# stm32f405rgt6_DB_Sheet.net
KiCad netlist of a schematic drawn in Altium Designer
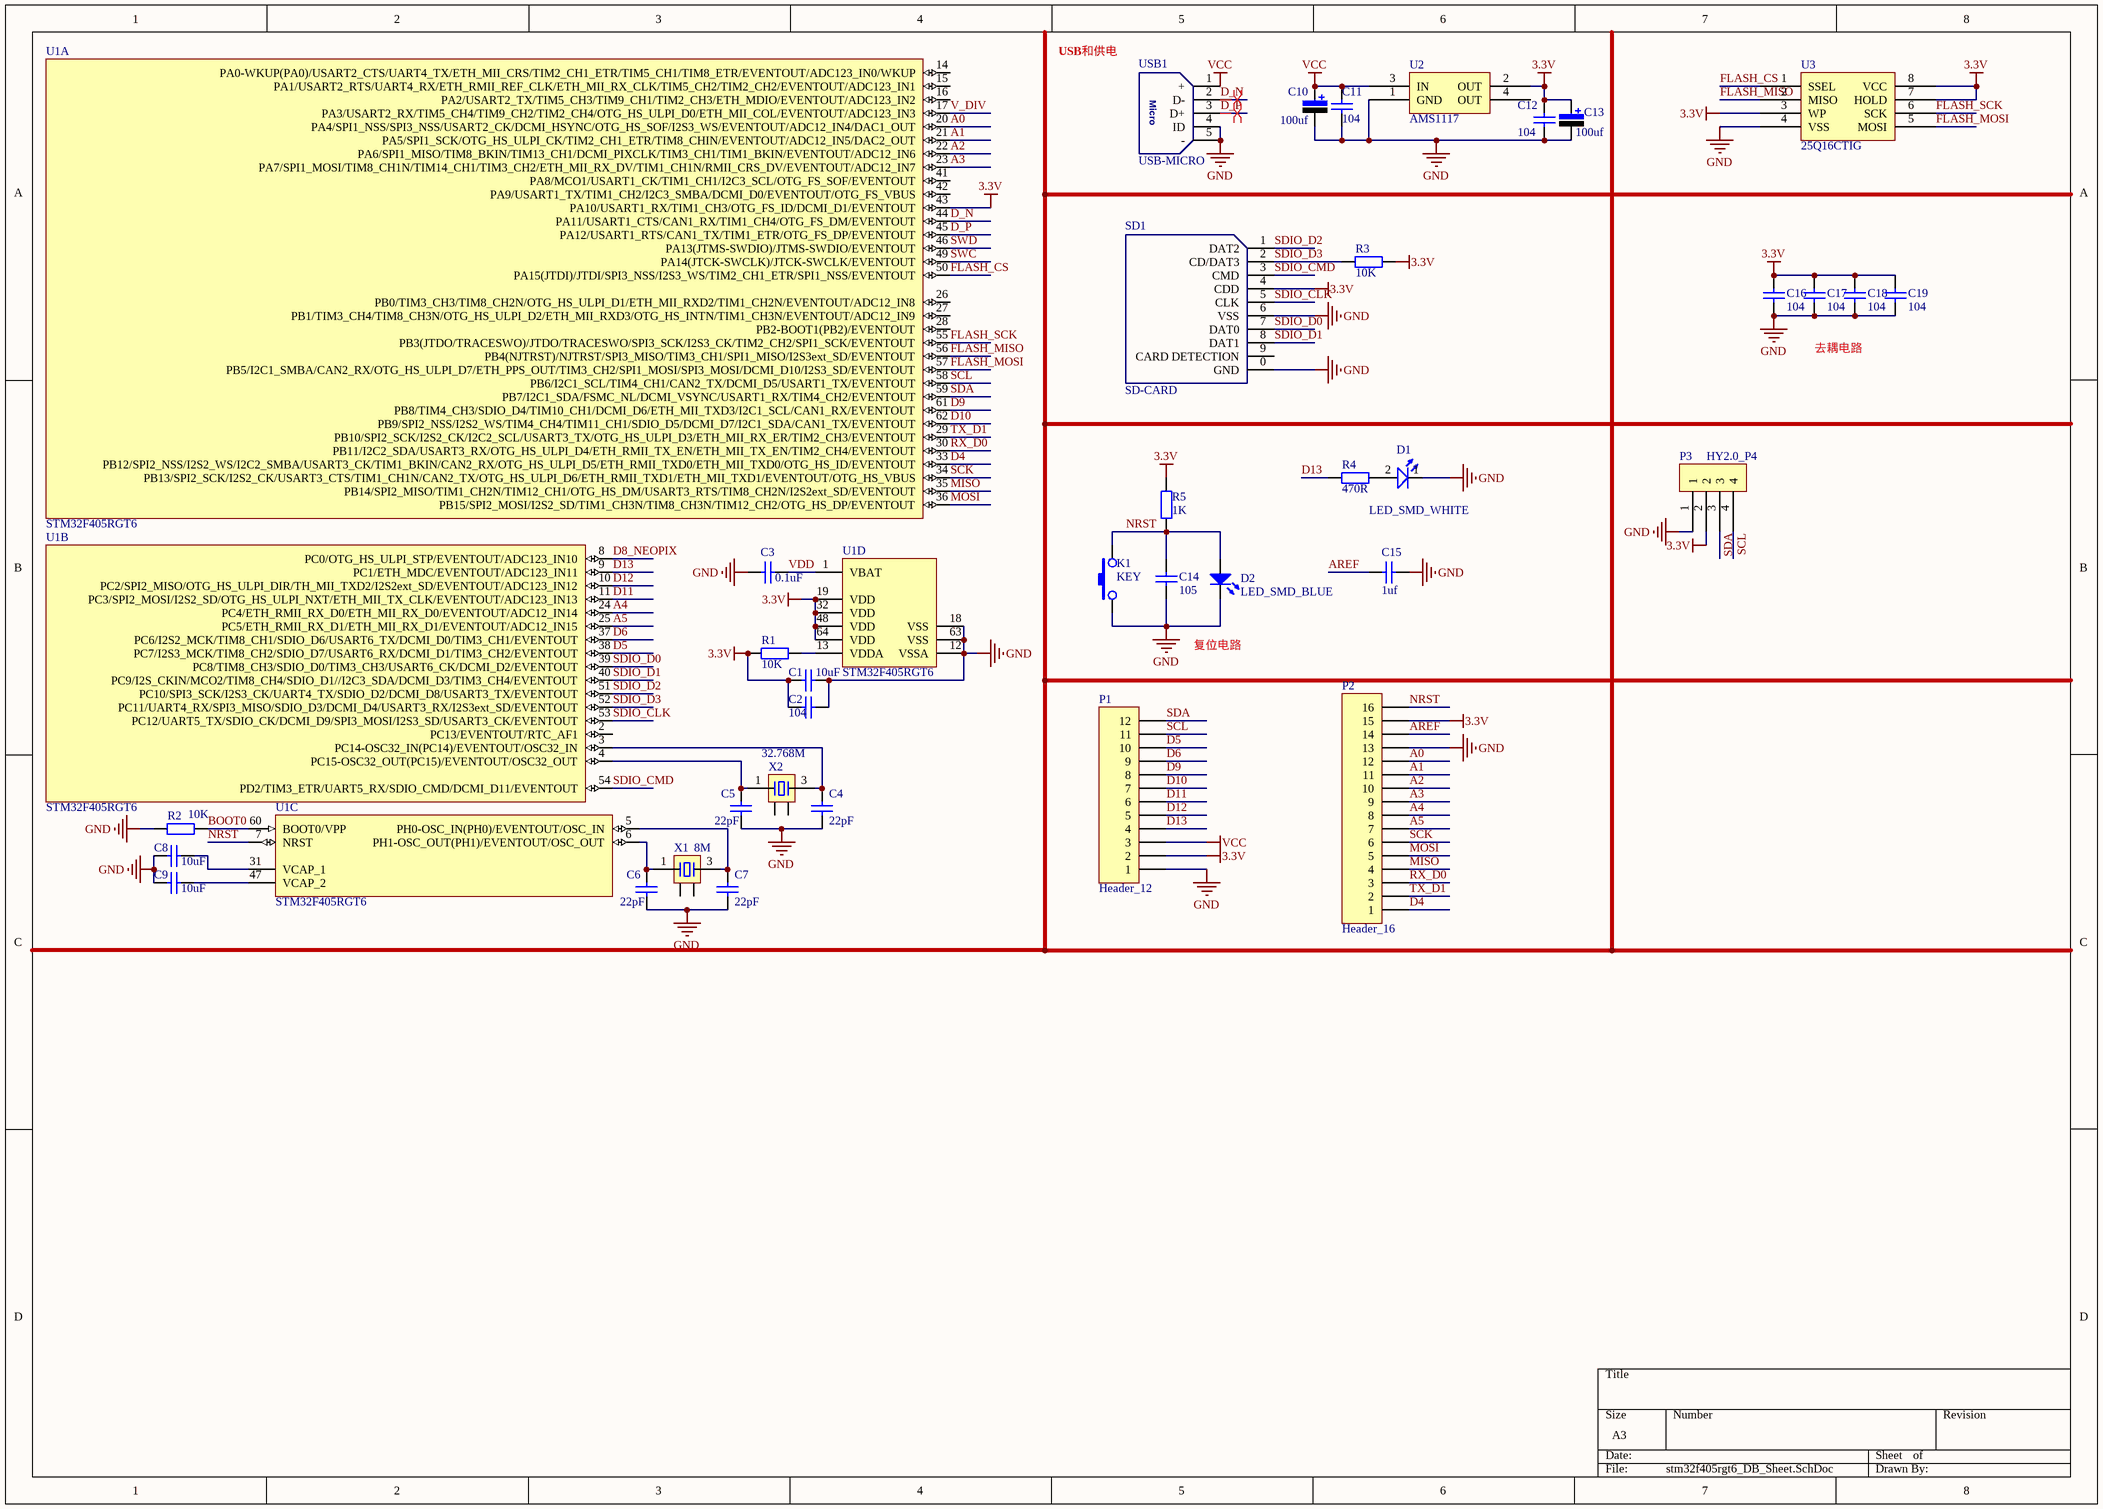
[diagram p0: stm32f405rgt6_DB_Sheet.SchDoc]

(export (version "E")
  (design (tool "Eeschema 10.0.6"))
  (components
    (comp (ref "C1")
      (value "10uF")
      (footprint "Cap-0603")
      (description "贴片陶瓷电容")
      (libsource (lib "Miscellaneous Base") (part "CAP"))
    )
    (comp (ref "C2")
      (value "104")
      (footprint "Cap-0603")
      (description "贴片陶瓷电容")
      (libsource (lib "Miscellaneous Base") (part "CAP"))
    )
    (comp (ref "C3")
      (value "0.1uF")
      (footprint "Cap-0603")
      (description "贴片陶瓷电容")
      (libsource (lib "Miscellaneous Base") (part "CAP"))
    )
    (comp (ref "C4")
      (value "22pF")
      (footprint "Cap-0603")
      (description "贴片陶瓷电容")
      (libsource (lib "Miscellaneous Base") (part "CAP"))
    )
    (comp (ref "C5")
      (value "22pF")
      (footprint "Cap-0603")
      (description "贴片陶瓷电容")
      (libsource (lib "Miscellaneous Base") (part "CAP"))
    )
    (comp (ref "C6")
      (value "22pF")
      (footprint "Cap-0603")
      (description "贴片陶瓷电容")
      (libsource (lib "Miscellaneous Base") (part "CAP"))
    )
    (comp (ref "C7")
      (value "22pF")
      (footprint "Cap-0603")
      (description "贴片陶瓷电容")
      (libsource (lib "Miscellaneous Base") (part "CAP"))
    )
    (comp (ref "C8")
      (value "10uF")
      (footprint "Cap-0603")
      (description "贴片陶瓷电容")
      (libsource (lib "Miscellaneous Base") (part "CAP"))
    )
    (comp (ref "C9")
      (value "10uF")
      (footprint "Cap-0603")
      (description "贴片陶瓷电容")
      (libsource (lib "Miscellaneous Base") (part "CAP"))
    )
    (comp (ref "C10")
      (value "100uf")
      (footprint "CAP_TAN_3216_A")
      (libsource (lib "最小系统元件库") (part "tan_cap"))
    )
    (comp (ref "C11") (value "104") (footprint "Cap-0603") (libsource (lib "最小系统元件库") (part "CAP")))
    (comp (ref "C12") (value "104") (footprint "Cap-0603") (libsource (lib "最小系统元件库") (part "CAP")))
    (comp (ref "C13")
      (value "100uf")
      (footprint "CAP_TAN_3216_A")
      (libsource (lib "最小系统元件库") (part "tan_cap"))
    )
    (comp (ref "C14") (value "105") (footprint "Cap-0603") (libsource (lib "最小系统元件库") (part "CAP")))
    (comp (ref "C15") (value "1uf") (footprint "Cap-0603") (libsource (lib "最小系统元件库") (part "CAP")))
    (comp (ref "C16") (value "104") (footprint "Cap-0603") (libsource (lib "最小系统元件库") (part "CAP")))
    (comp (ref "C17") (value "104") (footprint "Cap-0603") (libsource (lib "最小系统元件库") (part "CAP")))
    (comp (ref "C18") (value "104") (footprint "Cap-0603") (libsource (lib "最小系统元件库") (part "CAP")))
    (comp (ref "C19") (value "104") (footprint "Cap-0603") (libsource (lib "最小系统元件库") (part "CAP")))
    (comp (ref "D1")
      (value "LED_SMD_WHITE")
      (footprint "LED_0603_W")
      (description "发光二极管")
      (libsource (lib "Miscellaneous Transistor") (part "LED_SMD_WHITE"))
    )
    (comp (ref "D2")
      (value "LED_SMD_BLUE")
      (footprint "LED_0603_B")
      (description "发光二极管")
      (libsource (lib "Miscellaneous Transistor") (part "LED_SMD_BLUE"))
    )
    (comp (ref "K1")
      (value "KEY")
      (footprint "SW-SMD-2X4")
      (libsource (lib "Miscellaneous Switch") (part "KEY"))
    )
    (comp (ref "P1")
      (value "Header_12")
      (footprint "Header 2.54X12")
      (libsource (lib "Miscellaneous Header") (part "Header_12"))
    )
    (comp (ref "P2")
      (value "Header_16")
      (footprint "Header 2.54X16")
      (libsource (lib "Miscellaneous Header") (part "Header_16"))
    )
    (comp (ref "P3") (value "HY2.0_P4") (footprint "HY2.0_P4") (libsource (lib "HY2.0") (part "HY2.0_P4")))
    (comp (ref "R1")
      (value "10K")
      (footprint "Res-0603")
      (description "贴片电阻")
      (libsource (lib "Miscellaneous Base") (part "RES"))
    )
    (comp (ref "R2")
      (value "10K")
      (footprint "Res-0603")
      (description "贴片电阻")
      (libsource (lib "Miscellaneous Base") (part "RES"))
    )
    (comp (ref "R3")
      (value "10K")
      (footprint "Res-0603")
      (description "贴片电阻")
      (libsource (lib "Miscellaneous Base") (part "RES"))
    )
    (comp (ref "R4")
      (value "470R")
      (footprint "Res-0603")
      (description "贴片电阻")
      (libsource (lib "Miscellaneous Base") (part "RES"))
    )
    (comp (ref "R5")
      (value "1K")
      (footprint "Res-0603")
      (description "贴片电阻")
      (libsource (lib "") (part "RES_1"))
    )
    (comp (ref "SD1")
      (value "SD-CARD")
      (footprint "SD-CARD-Micro")
      (libsource (lib "Miscellaneous Socket") (part "SD-CARD"))
    )
    (comp (ref "U1")
      (value "STM32F405RGT6")
      (footprint "TQFP64_V")
      (libsource (lib "STMicroelectronics STM32 F4") (part "STM32F405RGT6"))
    )
    (comp (ref "U2") (value "AMS1117") (footprint "SOT89") (libsource (lib "最小系统元件库") (part "AMS1117")))
    (comp (ref "U3")
      (value "25Q16CTIG")
      (footprint "SOP8_M")
      (libsource (lib "25Q16CTIG") (part "25Q16CTIG"))
    )
    (comp (ref "USB1")
      (value "USB-MICRO")
      (footprint "USB-MICRO-SMD_C")
      (libsource (lib "Miscellaneous Socket") (part "USB-MICRO"))
    )
    (comp (ref "X1")
      (value "8M")
      (footprint "OSC 3225-4P")
      (description "4脚无源晶振")
      (libsource (lib "Miscellaneous XTAL") (part "XTAL-4P"))
    )
    (comp (ref "X2")
      (value "32.768M")
      (footprint "OSC 3225-4P")
      (description "4脚无源晶振")
      (libsource (lib "Miscellaneous XTAL") (part "XTAL-4P"))
    )
  )
  (nets
    (net (code "1") (name "/A0") (class "Default")
      (node (ref "P2") (pin "12") (pinfunction "12_12") (pintype "passive"))
      (node (ref "U1") (pin "20") (pinfunction "PA4/SPI1_NSS/SPI3_NSS/USART2_CK/DCMI_HSYNC/OTG_HS_SOF/I2S3_WS/EVENTOUT/ADC12_IN4/DAC1_OUT_20") (pintype "bidirectional"))
    )
    (net (code "2") (name "/A1") (class "Default")
      (node (ref "P2") (pin "11") (pinfunction "11_11") (pintype "passive"))
      (node (ref "U1") (pin "21") (pinfunction "PA5/SPI1_SCK/OTG_HS_ULPI_CK/TIM2_CH1_ETR/TIM8_CHIN/EVENTOUT/ADC12_IN5/DAC2_OUT_21") (pintype "bidirectional"))
    )
    (net (code "3") (name "/A2") (class "Default")
      (node (ref "P2") (pin "10") (pinfunction "10_10") (pintype "passive"))
      (node (ref "U1") (pin "22") (pinfunction "PA6/SPI1_MISO/TIM8_BKIN/TIM13_CH1/DCMI_PIXCLK/TIM3_CH1/TIM1_BKIN/EVENTOUT/ADC12_IN6_22") (pintype "bidirectional"))
    )
    (net (code "4") (name "/A3") (class "Default")
      (node (ref "P2") (pin "9") (pinfunction "9_9") (pintype "passive"))
      (node (ref "U1") (pin "23") (pinfunction "PA7/SPI1_MOSI/TIM8_CH1N/TIM14_CH1/TIM3_CH2/ETH_MII_RX_DV/TIM1_CH1N/RMII_CRS_DV/EVENTOUT/ADC12_IN7_23") (pintype "bidirectional"))
    )
    (net (code "5") (name "/A4") (class "Default")
      (node (ref "P2") (pin "8") (pinfunction "8_8") (pintype "passive"))
      (node (ref "U1") (pin "24") (pinfunction "PC4/ETH_RMII_RX_D0/ETH_MII_RX_D0/EVENTOUT/ADC12_IN14_24") (pintype "bidirectional"))
    )
    (net (code "6") (name "/A5") (class "Default")
      (node (ref "P2") (pin "7") (pinfunction "7_7") (pintype "passive"))
      (node (ref "U1") (pin "25") (pinfunction "PC5/ETH_RMII_RX_D1/ETH_MII_RX_D1/EVENTOUT/ADC12_IN15_25") (pintype "bidirectional"))
    )
    (net (code "7") (name "/AREF") (class "Default")
      (node (ref "C15") (pin "2") (pinfunction "2_2") (pintype "passive"))
      (node (ref "P2") (pin "14") (pinfunction "14_14") (pintype "passive"))
    )
    (net (code "8") (name "/BOOT0") (class "Default")
      (node (ref "R2") (pin "2") (pinfunction "2_2") (pintype "passive"))
      (node (ref "U1") (pin "60") (pinfunction "BOOT0/VPP_60") (pintype "input"))
    )
    (net (code "9") (name "/D4") (class "Default")
      (node (ref "P2") (pin "1") (pinfunction "1_1") (pintype "passive"))
      (node (ref "U1") (pin "33") (pinfunction "PB12/SPI2_NSS/I2S2_WS/I2C2_SMBA/USART3_CK/TIM1_BKIN/CAN2_RX/OTG_HS_ULPI_D5/ETH_RMII_TXD0/ETH_MII_TXD0/OTG_HS_ID/EVENTOUT_33") (pintype "bidirectional"))
    )
    (net (code "10") (name "/D5") (class "Default")
      (node (ref "P1") (pin "10") (pinfunction "10_10") (pintype "passive"))
      (node (ref "U1") (pin "38") (pinfunction "PC7/I2S3_MCK/TIM8_CH2/SDIO_D7/USART6_RX/DCMI_D1/TIM3_CH2/EVENTOUT_38") (pintype "bidirectional"))
    )
    (net (code "11") (name "/D6") (class "Default")
      (node (ref "P1") (pin "9") (pinfunction "9_9") (pintype "passive"))
      (node (ref "U1") (pin "37") (pinfunction "PC6/I2S2_MCK/TIM8_CH1/SDIO_D6/USART6_TX/DCMI_D0/TIM3_CH1/EVENTOUT_37") (pintype "bidirectional"))
    )
    (net (code "12") (name "/D8_NEOPIX") (class "Default")
      (node (ref "U1") (pin "8") (pinfunction "PC0/OTG_HS_ULPI_STP/EVENTOUT/ADC123_IN10_8") (pintype "bidirectional"))
    )
    (net (code "13") (name "/D9") (class "Default")
      (node (ref "P1") (pin "8") (pinfunction "8_8") (pintype "passive"))
      (node (ref "U1") (pin "61") (pinfunction "PB8/TIM4_CH3/SDIO_D4/TIM10_CH1/DCMI_D6/ETH_MII_TXD3/I2C1_SCL/CAN1_RX/EVENTOUT_61") (pintype "bidirectional"))
    )
    (net (code "14") (name "/D10") (class "Default")
      (node (ref "P1") (pin "7") (pinfunction "7_7") (pintype "passive"))
      (node (ref "U1") (pin "62") (pinfunction "PB9/SPI2_NSS/I2S2_WS/TIM4_CH4/TIM11_CH1/SDIO_D5/DCMI_D7/I2C1_SDA/CAN1_TX/EVENTOUT_62") (pintype "bidirectional"))
    )
    (net (code "15") (name "/D11") (class "Default")
      (node (ref "P1") (pin "6") (pinfunction "6_6") (pintype "passive"))
      (node (ref "U1") (pin "11") (pinfunction "PC3/SPI2_MOSI/I2S2_SD/OTG_HS_ULPI_NXT/ETH_MII_TX_CLK/EVENTOUT/ADC123_IN13_11") (pintype "bidirectional"))
    )
    (net (code "16") (name "/D12") (class "Default")
      (node (ref "P1") (pin "5") (pinfunction "5_5") (pintype "passive"))
      (node (ref "U1") (pin "10") (pinfunction "PC2/SPI2_MISO/OTG_HS_ULPI_DIR/TH_MII_TXD2/I2S2ext_SD/EVENTOUT/ADC123_IN12_10") (pintype "bidirectional"))
    )
    (net (code "17") (name "/D13") (class "Default")
      (node (ref "P1") (pin "4") (pinfunction "4_4") (pintype "passive"))
      (node (ref "R4") (pin "1") (pinfunction "1_1") (pintype "passive"))
      (node (ref "U1") (pin "9") (pinfunction "PC1/ETH_MDC/EVENTOUT/ADC123_IN11_9") (pintype "bidirectional"))
    )
    (net (code "18") (name "/D_N") (class "Default")
      (node (ref "U1") (pin "44") (pinfunction "PA11/USART1_CTS/CAN1_RX/TIM1_CH4/OTG_FS_DM/EVENTOUT_44") (pintype "bidirectional"))
      (node (ref "USB1") (pin "2") (pinfunction "D-_2") (pintype "passive"))
    )
    (net (code "19") (name "/D_P") (class "Default")
      (node (ref "U1") (pin "45") (pinfunction "PA12/USART1_RTS/CAN1_TX/TIM1_ETR/OTG_FS_DP/EVENTOUT_45") (pintype "bidirectional"))
      (node (ref "USB1") (pin "3") (pinfunction "D+_3") (pintype "passive"))
    )
    (net (code "20") (name "/FLASH_CS") (class "Default")
      (node (ref "U1") (pin "50") (pinfunction "PA15(JTDI)/JTDI/SPI3_NSS/I2S3_WS/TIM2_CH1_ETR/SPI1_NSS/EVENTOUT_50") (pintype "bidirectional"))
      (node (ref "U3") (pin "1") (pinfunction "SSEL_1") (pintype "passive"))
    )
    (net (code "21") (name "/FLASH_MISO") (class "Default")
      (node (ref "U1") (pin "56") (pinfunction "PB4(NJTRST)/NJTRST/SPI3_MISO/TIM3_CH1/SPI1_MISO/I2S3ext_SD/EVENTOUT_56") (pintype "bidirectional"))
      (node (ref "U3") (pin "2") (pinfunction "MISO_2") (pintype "passive"))
    )
    (net (code "22") (name "/FLASH_MOSI") (class "Default")
      (node (ref "U1") (pin "57") (pinfunction "PB5/I2C1_SMBA/CAN2_RX/OTG_HS_ULPI_D7/ETH_PPS_OUT/TIM3_CH2/SPI1_MOSI/SPI3_MOSI/DCMI_D10/I2S3_SD/EVENTOUT_57") (pintype "bidirectional"))
      (node (ref "U3") (pin "5") (pinfunction "MOSI_5") (pintype "passive"))
    )
    (net (code "23") (name "/FLASH_SCK") (class "Default")
      (node (ref "U1") (pin "55") (pinfunction "PB3(JTDO/TRACESWO)/JTDO/TRACESWO/SPI3_SCK/I2S3_CK/TIM2_CH2/SPI1_SCK/EVENTOUT_55") (pintype "bidirectional"))
      (node (ref "U3") (pin "6") (pinfunction "SCK_6") (pintype "passive"))
    )
    (net (code "24") (name "/MISO") (class "Default")
      (node (ref "P2") (pin "4") (pinfunction "4_4") (pintype "passive"))
      (node (ref "U1") (pin "35") (pinfunction "PB14/SPI2_MISO/TIM1_CH2N/TIM12_CH1/OTG_HS_DM/USART3_RTS/TIM8_CH2N/I2S2ext_SD/EVENTOUT_35") (pintype "bidirectional"))
    )
    (net (code "25") (name "/MOSI") (class "Default")
      (node (ref "P2") (pin "5") (pinfunction "5_5") (pintype "passive"))
      (node (ref "U1") (pin "36") (pinfunction "PB15/SPI2_MOSI/I2S2_SD/TIM1_CH3N/TIM8_CH3N/TIM12_CH2/OTG_HS_DP/EVENTOUT_36") (pintype "bidirectional"))
    )
    (net (code "26") (name "/NRST") (class "Default")
      (node (ref "C14") (pin "2") (pinfunction "2_2") (pintype "passive"))
      (node (ref "D2") (pin "2") (pinfunction "A_2") (pintype "passive"))
      (node (ref "K1") (pin "3") (pinfunction "3_3") (pintype "passive"))
      (node (ref "P2") (pin "16") (pinfunction "16_16") (pintype "passive"))
      (node (ref "R5") (pin "2") (pinfunction "2_2") (pintype "passive"))
      (node (ref "U1") (pin "7") (pinfunction "NRST_7") (pintype "bidirectional"))
    )
    (net (code "27") (name "/RX_D0") (class "Default")
      (node (ref "P2") (pin "3") (pinfunction "3_3") (pintype "passive"))
      (node (ref "U1") (pin "30") (pinfunction "PB11/I2C2_SDA/USART3_RX/OTG_HS_ULPI_D4/ETH_RMII_TX_EN/ETH_MII_TX_EN/TIM2_CH4/EVENTOUT_30") (pintype "bidirectional"))
    )
    (net (code "28") (name "/SCK") (class "Default")
      (node (ref "P2") (pin "6") (pinfunction "6_6") (pintype "passive"))
      (node (ref "U1") (pin "34") (pinfunction "PB13/SPI2_SCK/I2S2_CK/USART3_CTS/TIM1_CH1N/CAN2_TX/OTG_HS_ULPI_D6/ETH_RMII_TXD1/ETH_MII_TXD1/EVENTOUT/OTG_HS_VBUS_34") (pintype "bidirectional"))
    )
    (net (code "29") (name "/SCL") (class "Default")
      (node (ref "P1") (pin "11") (pinfunction "11_11") (pintype "passive"))
      (node (ref "P3") (pin "4") (pinfunction "4_4") (pintype "passive"))
      (node (ref "U1") (pin "58") (pinfunction "PB6/I2C1_SCL/TIM4_CH1/CAN2_TX/DCMI_D5/USART1_TX/EVENTOUT_58") (pintype "bidirectional"))
    )
    (net (code "30") (name "/SDA") (class "Default")
      (node (ref "P1") (pin "12") (pinfunction "12_12") (pintype "passive"))
      (node (ref "P3") (pin "3") (pinfunction "3_3") (pintype "passive"))
      (node (ref "U1") (pin "59") (pinfunction "PB7/I2C1_SDA/FSMC_NL/DCMI_VSYNC/USART1_RX/TIM4_CH2/EVENTOUT_59") (pintype "bidirectional"))
    )
    (net (code "31") (name "/SDIO_CLK") (class "Default")
      (node (ref "SD1") (pin "5") (pinfunction "CLK_5") (pintype "passive"))
      (node (ref "U1") (pin "53") (pinfunction "PC12/UART5_TX/SDIO_CK/DCMI_D9/SPI3_MOSI/I2S3_SD/USART3_CK/EVENTOUT_53") (pintype "bidirectional"))
    )
    (net (code "32") (name "/SDIO_CMD") (class "Default")
      (node (ref "SD1") (pin "3") (pinfunction "CMD_3") (pintype "passive"))
      (node (ref "U1") (pin "54") (pinfunction "PD2/TIM3_ETR/UART5_RX/SDIO_CMD/DCMI_D11/EVENTOUT_54") (pintype "bidirectional"))
    )
    (net (code "33") (name "/SDIO_D0") (class "Default")
      (node (ref "SD1") (pin "7") (pinfunction "DAT0_7") (pintype "passive"))
      (node (ref "U1") (pin "39") (pinfunction "PC8/TIM8_CH3/SDIO_D0/TIM3_CH3/USART6_CK/DCMI_D2/EVENTOUT_39") (pintype "bidirectional"))
    )
    (net (code "34") (name "/SDIO_D1") (class "Default")
      (node (ref "SD1") (pin "8") (pinfunction "DAT1_8") (pintype "passive"))
      (node (ref "U1") (pin "40") (pinfunction "PC9/I2S_CKIN/MCO2/TIM8_CH4/SDIO_D1//I2C3_SDA/DCMI_D3/TIM3_CH4/EVENTOUT_40") (pintype "bidirectional"))
    )
    (net (code "35") (name "/SDIO_D2") (class "Default")
      (node (ref "SD1") (pin "1") (pinfunction "DAT2_1") (pintype "passive"))
      (node (ref "U1") (pin "51") (pinfunction "PC10/SPI3_SCK/I2S3_CK/UART4_TX/SDIO_D2/DCMI_D8/USART3_TX/EVENTOUT_51") (pintype "bidirectional"))
    )
    (net (code "36") (name "/SDIO_D3") (class "Default")
      (node (ref "R3") (pin "1") (pinfunction "1_1") (pintype "passive"))
      (node (ref "SD1") (pin "2") (pinfunction "CD/DAT3_2") (pintype "passive"))
      (node (ref "U1") (pin "52") (pinfunction "PC11/UART4_RX/SPI3_MISO/SDIO_D3/DCMI_D4/USART3_RX/I2S3ext_SD/EVENTOUT_52") (pintype "bidirectional"))
    )
    (net (code "37") (name "/SWC") (class "Default")
      (node (ref "U1") (pin "49") (pinfunction "PA14(JTCK-SWCLK)/JTCK-SWCLK/EVENTOUT_49") (pintype "bidirectional"))
    )
    (net (code "38") (name "/SWD") (class "Default")
      (node (ref "U1") (pin "46") (pinfunction "PA13(JTMS-SWDIO)/JTMS-SWDIO/EVENTOUT_46") (pintype "bidirectional"))
    )
    (net (code "39") (name "/TX_D1") (class "Default")
      (node (ref "P2") (pin "2") (pinfunction "2_2") (pintype "passive"))
      (node (ref "U1") (pin "29") (pinfunction "PB10/SPI2_SCK/I2S2_CK/I2C2_SCL/USART3_TX/OTG_HS_ULPI_D3/ETH_MII_RX_ER/TIM2_CH3/EVENTOUT_29") (pintype "bidirectional"))
    )
    (net (code "40") (name "/VDD") (class "Default")
      (node (ref "C3") (pin "2") (pinfunction "2_2") (pintype "passive"))
      (node (ref "U1") (pin "1") (pinfunction "VBAT_1") (pintype "power_in"))
    )
    (net (code "41") (name "/V_DIV") (class "Default")
      (node (ref "U1") (pin "17") (pinfunction "PA3/USART2_RX/TIM5_CH4/TIM9_CH2/TIM2_CH4/OTG_HS_ULPI_D0/ETH_MII_COL/EVENTOUT/ADC123_IN3_17") (pintype "bidirectional"))
    )
    (net (code "42") (name "3.3V") (class "Default")
      (node (ref "C1") (pin "1") (pinfunction "1_1") (pintype "passive"))
      (node (ref "C12") (pin "2") (pinfunction "2_2") (pintype "passive"))
      (node (ref "C13") (pin "1") (pinfunction "1_1") (pintype "passive"))
      (node (ref "C16") (pin "2") (pinfunction "2_2") (pintype "passive"))
      (node (ref "C17") (pin "2") (pinfunction "2_2") (pintype "passive"))
      (node (ref "C18") (pin "2") (pinfunction "2_2") (pintype "passive"))
      (node (ref "C19") (pin "2") (pinfunction "2_2") (pintype "passive"))
      (node (ref "C2") (pin "1") (pinfunction "1_1") (pintype "passive"))
      (node (ref "P1") (pin "2") (pinfunction "2_2") (pintype "passive"))
      (node (ref "P2") (pin "15") (pinfunction "15_15") (pintype "passive"))
      (node (ref "P3") (pin "2") (pinfunction "2_2") (pintype "passive"))
      (node (ref "R1") (pin "1") (pinfunction "1_1") (pintype "passive"))
      (node (ref "R3") (pin "2") (pinfunction "2_2") (pintype "passive"))
      (node (ref "R5") (pin "1") (pinfunction "1_1") (pintype "passive"))
      (node (ref "SD1") (pin "4") (pinfunction "CDD_4") (pintype "passive"))
      (node (ref "U1") (pin "19") (pinfunction "VDD_19") (pintype "power_in"))
      (node (ref "U1") (pin "32") (pinfunction "VDD_32") (pintype "power_in"))
      (node (ref "U1") (pin "43") (pinfunction "PA10/USART1_RX/TIM1_CH3/OTG_FS_ID/DCMI_D1/EVENTOUT_43") (pintype "bidirectional"))
      (node (ref "U1") (pin "48") (pinfunction "VDD_48") (pintype "power_in"))
      (node (ref "U1") (pin "64") (pinfunction "VDD_64") (pintype "power_in"))
      (node (ref "U2") (pin "2") (pinfunction "OUT_2") (pintype "passive"))
      (node (ref "U3") (pin "3") (pinfunction "WP_3") (pintype "passive"))
      (node (ref "U3") (pin "7") (pinfunction "HOLD_7") (pintype "passive"))
      (node (ref "U3") (pin "8") (pinfunction "VCC_8") (pintype "passive"))
    )
    (net (code "43") (name "GND") (class "Default")
      (node (ref "C1") (pin "2") (pinfunction "2_2") (pintype "passive"))
      (node (ref "C10") (pin "2") (pinfunction "2_2") (pintype "passive"))
      (node (ref "C11") (pin "1") (pinfunction "1_1") (pintype "passive"))
      (node (ref "C12") (pin "1") (pinfunction "1_1") (pintype "passive"))
      (node (ref "C13") (pin "2") (pinfunction "2_2") (pintype "passive"))
      (node (ref "C14") (pin "1") (pinfunction "1_1") (pintype "passive"))
      (node (ref "C15") (pin "1") (pinfunction "1_1") (pintype "passive"))
      (node (ref "C16") (pin "1") (pinfunction "1_1") (pintype "passive"))
      (node (ref "C17") (pin "1") (pinfunction "1_1") (pintype "passive"))
      (node (ref "C18") (pin "1") (pinfunction "1_1") (pintype "passive"))
      (node (ref "C19") (pin "1") (pinfunction "1_1") (pintype "passive"))
      (node (ref "C2") (pin "2") (pinfunction "2_2") (pintype "passive"))
      (node (ref "C3") (pin "1") (pinfunction "1_1") (pintype "passive"))
      (node (ref "C4") (pin "1") (pinfunction "1_1") (pintype "passive"))
      (node (ref "C5") (pin "2") (pinfunction "2_2") (pintype "passive"))
      (node (ref "C6") (pin "2") (pinfunction "2_2") (pintype "passive"))
      (node (ref "C7") (pin "1") (pinfunction "1_1") (pintype "passive"))
      (node (ref "C8") (pin "1") (pinfunction "1_1") (pintype "passive"))
      (node (ref "C9") (pin "1") (pinfunction "1_1") (pintype "passive"))
      (node (ref "D1") (pin "1") (pinfunction "K_1") (pintype "passive"))
      (node (ref "D2") (pin "1") (pinfunction "K_1") (pintype "passive"))
      (node (ref "K1") (pin "1") (pinfunction "1_1") (pintype "passive"))
      (node (ref "P1") (pin "1") (pinfunction "1_1") (pintype "passive"))
      (node (ref "P2") (pin "13") (pinfunction "13_13") (pintype "passive"))
      (node (ref "P3") (pin "1") (pinfunction "1_1") (pintype "passive"))
      (node (ref "R2") (pin "1") (pinfunction "1_1") (pintype "passive"))
      (node (ref "SD1") (pin "0") (pinfunction "GND_0") (pintype "passive"))
      (node (ref "SD1") (pin "6") (pinfunction "VSS_6") (pintype "passive"))
      (node (ref "U1") (pin "12") (pinfunction "VSSA_12") (pintype "power_in"))
      (node (ref "U1") (pin "18") (pinfunction "VSS_18") (pintype "power_in"))
      (node (ref "U1") (pin "63") (pinfunction "VSS_63") (pintype "power_in"))
      (node (ref "U2") (pin "1") (pinfunction "GND_1") (pintype "passive"))
      (node (ref "U3") (pin "4") (pinfunction "VSS_4") (pintype "passive"))
      (node (ref "USB1") (pin "4") (pinfunction "ID_4") (pintype "passive"))
      (node (ref "USB1") (pin "5") (pinfunction "-_5") (pintype "passive"))
    )
    (net (code "44") (name "Net-(D1-A)") (class "Default")
      (node (ref "D1") (pin "2") (pinfunction "A_2") (pintype "passive"))
      (node (ref "R4") (pin "2") (pinfunction "2_2") (pintype "passive"))
    )
    (net (code "45") (name "Net-(U1B-PC14-OSC32_IN(PC14){slash}EVENTOUT{slash}OSC32_IN)") (class "Default")
      (node (ref "C4") (pin "2") (pinfunction "2_2") (pintype "passive"))
      (node (ref "U1") (pin "3") (pinfunction "PC14-OSC32_IN(PC14)/EVENTOUT/OSC32_IN_3") (pintype "bidirectional"))
      (node (ref "X2") (pin "3") (pinfunction "3_3") (pintype "passive"))
    )
    (net (code "46") (name "Net-(U1B-PC15-OSC32_OUT(PC15){slash}EVENTOUT{slash}OSC32_OUT)") (class "Default")
      (node (ref "C5") (pin "1") (pinfunction "1_1") (pintype "passive"))
      (node (ref "U1") (pin "4") (pinfunction "PC15-OSC32_OUT(PC15)/EVENTOUT/OSC32_OUT_4") (pintype "bidirectional"))
      (node (ref "X2") (pin "1") (pinfunction "1_1") (pintype "passive"))
    )
    (net (code "47") (name "Net-(U1C-PH0-OSC_IN(PH0){slash}EVENTOUT{slash}OSC_IN)") (class "Default")
      (node (ref "C7") (pin "2") (pinfunction "2_2") (pintype "passive"))
      (node (ref "U1") (pin "5") (pinfunction "PH0-OSC_IN(PH0)/EVENTOUT/OSC_IN_5") (pintype "bidirectional"))
      (node (ref "X1") (pin "3") (pinfunction "3_3") (pintype "passive"))
    )
    (net (code "48") (name "Net-(U1C-PH1-OSC_OUT(PH1){slash}EVENTOUT{slash}OSC_OUT)") (class "Default")
      (node (ref "C6") (pin "1") (pinfunction "1_1") (pintype "passive"))
      (node (ref "U1") (pin "6") (pinfunction "PH1-OSC_OUT(PH1)/EVENTOUT/OSC_OUT_6") (pintype "bidirectional"))
      (node (ref "X1") (pin "1") (pinfunction "1_1") (pintype "passive"))
    )
    (net (code "49") (name "Net-(U1C-VCAP_1)") (class "Default")
      (node (ref "C8") (pin "2") (pinfunction "2_2") (pintype "passive"))
      (node (ref "U1") (pin "31") (pinfunction "VCAP_1_31") (pintype "power_in"))
    )
    (net (code "50") (name "Net-(U1C-VCAP_2)") (class "Default")
      (node (ref "C9") (pin "2") (pinfunction "2_2") (pintype "passive"))
      (node (ref "U1") (pin "47") (pinfunction "VCAP_2_47") (pintype "power_in"))
    )
    (net (code "51") (name "Net-(U1D-VDDA)") (class "Default")
      (node (ref "R1") (pin "2") (pinfunction "2_2") (pintype "passive"))
      (node (ref "U1") (pin "13") (pinfunction "VDDA_13") (pintype "power_in"))
    )
    (net (code "52") (name "VCC") (class "Default")
      (node (ref "C10") (pin "1") (pinfunction "1_1") (pintype "passive"))
      (node (ref "C11") (pin "2") (pinfunction "2_2") (pintype "passive"))
      (node (ref "P1") (pin "3") (pinfunction "3_3") (pintype "passive"))
      (node (ref "U2") (pin "3") (pinfunction "IN_3") (pintype "passive"))
      (node (ref "USB1") (pin "1") (pinfunction "+_1") (pintype "passive"))
    )
    (net (code "53") (name "unconnected-(SD1-CARD_DETECTION-Pad9)") (class "Default")
      (node (ref "SD1") (pin "9") (pinfunction "CARD_DETECTION_9") (pintype "passive"))
    )
    (net (code "54") (name "unconnected-(U1A-PA0-WKUP(PA0){slash}USART2_CTS{slash}UART4_TX{slash}ETH_MII_CRS{slash}TIM2_CH1_ETR{slash}TIM5_CH1{slash}TIM8_ETR{slash}EVENTOUT{slash}ADC123_IN0{slash}WKUP-Pad14)") (class "Default")
      (node (ref "U1") (pin "14") (pinfunction "PA0-WKUP(PA0)/USART2_CTS/UART4_TX/ETH_MII_CRS/TIM2_CH1_ETR/TIM5_CH1/TIM8_ETR/EVENTOUT/ADC123_IN0/WKUP_14") (pintype "bidirectional"))
    )
    (net (code "55") (name "unconnected-(U1A-PA1{slash}USART2_RTS{slash}UART4_RX{slash}ETH_RMII_REF_CLK{slash}ETH_MII_RX_CLK{slash}TIM5_CH2{slash}TIM2_CH2{slash}EVENTOUT{slash}ADC123_IN1-Pad15)") (class "Default")
      (node (ref "U1") (pin "15") (pinfunction "PA1/USART2_RTS/UART4_RX/ETH_RMII_REF_CLK/ETH_MII_RX_CLK/TIM5_CH2/TIM2_CH2/EVENTOUT/ADC123_IN1_15") (pintype "bidirectional"))
    )
    (net (code "56") (name "unconnected-(U1A-PA2{slash}USART2_TX{slash}TIM5_CH3{slash}TIM9_CH1{slash}TIM2_CH3{slash}ETH_MDIO{slash}EVENTOUT{slash}ADC123_IN2-Pad16)") (class "Default")
      (node (ref "U1") (pin "16") (pinfunction "PA2/USART2_TX/TIM5_CH3/TIM9_CH1/TIM2_CH3/ETH_MDIO/EVENTOUT/ADC123_IN2_16") (pintype "bidirectional"))
    )
    (net (code "57") (name "unconnected-(U1A-PA8{slash}MCO1{slash}USART1_CK{slash}TIM1_CH1{slash}I2C3_SCL{slash}OTG_FS_SOF{slash}EVENTOUT-Pad41)") (class "Default")
      (node (ref "U1") (pin "41") (pinfunction "PA8/MCO1/USART1_CK/TIM1_CH1/I2C3_SCL/OTG_FS_SOF/EVENTOUT_41") (pintype "bidirectional"))
    )
    (net (code "58") (name "unconnected-(U1A-PA9{slash}USART1_TX{slash}TIM1_CH2{slash}I2C3_SMBA{slash}DCMI_D0{slash}EVENTOUT{slash}OTG_FS_VBUS-Pad42)") (class "Default")
      (node (ref "U1") (pin "42") (pinfunction "PA9/USART1_TX/TIM1_CH2/I2C3_SMBA/DCMI_D0/EVENTOUT/OTG_FS_VBUS_42") (pintype "bidirectional"))
    )
    (net (code "59") (name "unconnected-(U1A-PB0{slash}TIM3_CH3{slash}TIM8_CH2N{slash}OTG_HS_ULPI_D1{slash}ETH_MII_RXD2{slash}TIM1_CH2N{slash}EVENTOUT{slash}ADC12_IN8-Pad26)") (class "Default")
      (node (ref "U1") (pin "26") (pinfunction "PB0/TIM3_CH3/TIM8_CH2N/OTG_HS_ULPI_D1/ETH_MII_RXD2/TIM1_CH2N/EVENTOUT/ADC12_IN8_26") (pintype "bidirectional"))
    )
    (net (code "60") (name "unconnected-(U1A-PB1{slash}TIM3_CH4{slash}TIM8_CH3N{slash}OTG_HS_ULPI_D2{slash}ETH_MII_RXD3{slash}OTG_HS_INTN{slash}TIM1_CH3N{slash}EVENTOUT{slash}ADC12_IN9-Pad27)") (class "Default")
      (node (ref "U1") (pin "27") (pinfunction "PB1/TIM3_CH4/TIM8_CH3N/OTG_HS_ULPI_D2/ETH_MII_RXD3/OTG_HS_INTN/TIM1_CH3N/EVENTOUT/ADC12_IN9_27") (pintype "bidirectional"))
    )
    (net (code "61") (name "unconnected-(U1A-PB2-BOOT1(PB2){slash}EVENTOUT-Pad28)") (class "Default")
      (node (ref "U1") (pin "28") (pinfunction "PB2-BOOT1(PB2)/EVENTOUT_28") (pintype "bidirectional"))
    )
    (net (code "62") (name "unconnected-(U1B-PC13{slash}EVENTOUT{slash}RTC_AF1-Pad2)") (class "Default")
      (node (ref "U1") (pin "2") (pinfunction "PC13/EVENTOUT/RTC_AF1_2") (pintype "bidirectional"))
    )
    (net (code "63") (name "unconnected-(U2-OUT-Pad4)") (class "Default")
      (node (ref "U2") (pin "4") (pinfunction "OUT_4") (pintype "passive"))
    )
    (net (code "64") (name "unconnected-(X1-Pad2)") (class "Default")
      (node (ref "X1") (pin "2") (pinfunction "2_2") (pintype "passive"))
    )
    (net (code "65") (name "unconnected-(X1-Pad4)") (class "Default")
      (node (ref "X1") (pin "4") (pinfunction "4_4") (pintype "passive"))
    )
    (net (code "66") (name "unconnected-(X2-Pad2)") (class "Default")
      (node (ref "X2") (pin "2") (pinfunction "2_2") (pintype "passive"))
    )
    (net (code "67") (name "unconnected-(X2-Pad4)") (class "Default")
      (node (ref "X2") (pin "4") (pinfunction "4_4") (pintype "passive"))
    )
  )
)
